# BT_magnetic_switch.net
KiCad netlist of a schematic drawn in EAGLE
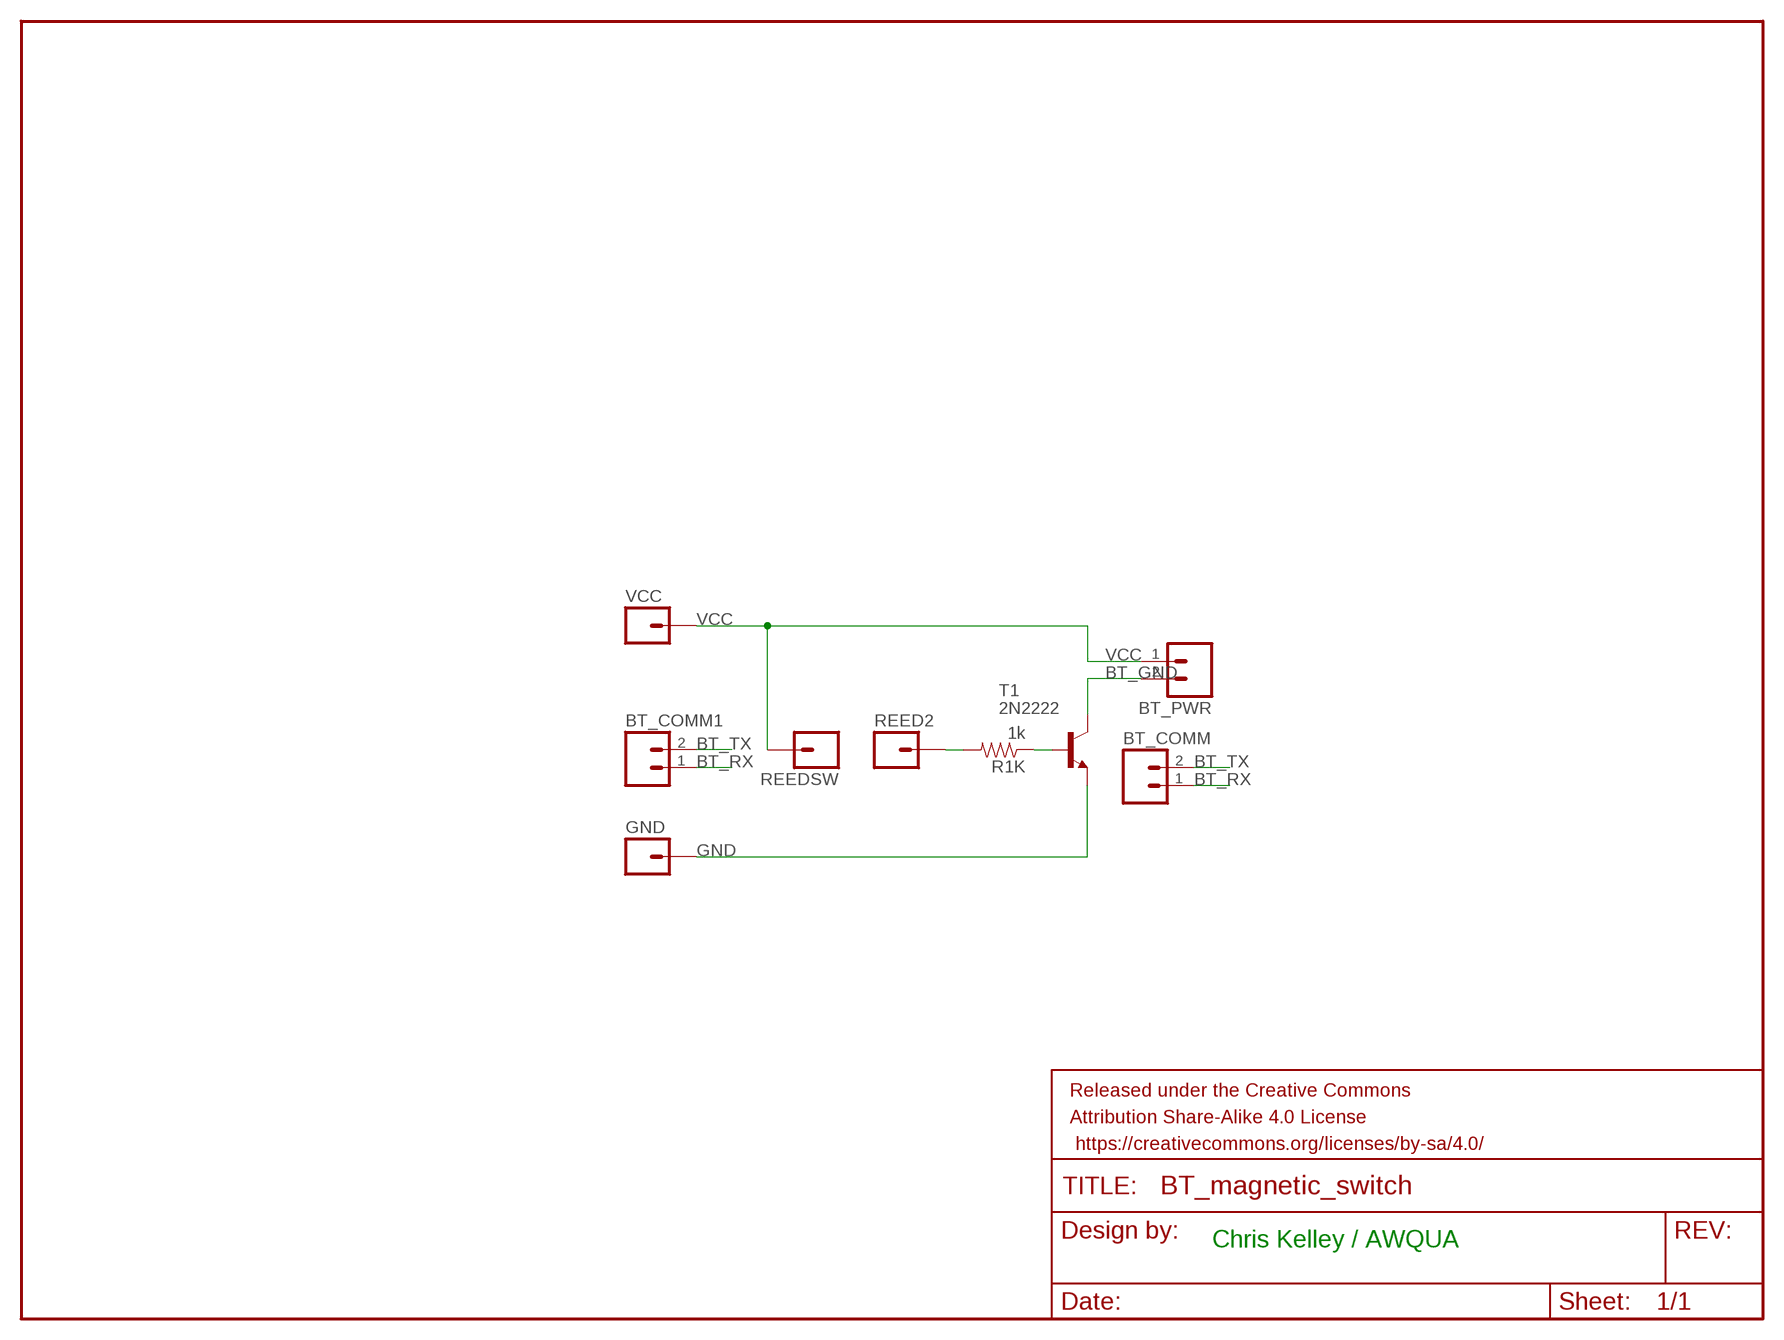
[diagram p0: schematic, sheet 1]

(export (version "E")
  (design (tool "Eeschema 10.0.6"))
  (components
    (comp (ref "BT_COMM")
      (value "M02PTH")
      (footprint "eagle-import:1X02")
      (libsource (lib "eagle-import") (part "M02PTH"))
    )
    (comp (ref "BT_COMM1")
      (value "M02PTH")
      (footprint "eagle-import:1X02")
      (libsource (lib "eagle-import") (part "M02PTH"))
    )
    (comp (ref "BT_PWR")
      (value "M02PTH")
      (footprint "eagle-import:1X02")
      (libsource (lib "eagle-import") (part "M02PTH"))
    )
    (comp (ref "FRAME1")
      (value "FRAME-LETTER")
      (footprint "eagle-import:CREATIVE_COMMONS")
      (libsource (lib "eagle-import") (part "FRAME-LETTER"))
    )
    (comp (ref "GND")
      (value "M01PTH")
      (footprint "eagle-import:1X01")
      (libsource (lib "eagle-import") (part "M01PTH"))
    )
    (comp (ref "R1K")
      (value "1k")
      (footprint "eagle-import:0603-RES")
      (libsource (lib "eagle-import") (part "RESISTOR0603-RES"))
    )
    (comp (ref "REED2")
      (value "M01PTH")
      (footprint "eagle-import:1X01")
      (libsource (lib "eagle-import") (part "M01PTH"))
    )
    (comp (ref "REEDSW")
      (value "M01PTH")
      (footprint "eagle-import:1X01")
      (libsource (lib "eagle-import") (part "M01PTH"))
    )
    (comp (ref "T1")
      (value "2N2222")
      (footprint "eagle-import:TO92-EBC-OVAL")
      (libsource (lib "eagle-import") (part "2N2222"))
    )
    (comp (ref "VCC")
      (value "M01PTH")
      (footprint "eagle-import:1X01")
      (libsource (lib "eagle-import") (part "M01PTH"))
    )
  )
  (nets
    (net (code "1") (name "/BT_GND") (class "Default")
      (node (ref "BT_PWR") (pin "2") (pinfunction "2_2") (pintype "passive"))
      (node (ref "T1") (pin "C") (pinfunction "C_C") (pintype "passive"))
    )
    (net (code "2") (name "/BT_RX") (class "Default")
      (node (ref "BT_COMM") (pin "1") (pinfunction "1_1") (pintype "passive"))
      (node (ref "BT_COMM1") (pin "1") (pinfunction "1_1") (pintype "passive"))
    )
    (net (code "3") (name "/BT_TX") (class "Default")
      (node (ref "BT_COMM") (pin "2") (pinfunction "2_2") (pintype "passive"))
      (node (ref "BT_COMM1") (pin "2") (pinfunction "2_2") (pintype "passive"))
    )
    (net (code "4") (name "/GND") (class "Default")
      (node (ref "GND") (pin "1") (pinfunction "1_1") (pintype "passive"))
      (node (ref "T1") (pin "E") (pinfunction "E_E") (pintype "passive"))
    )
    (net (code "5") (name "/VCC") (class "Default")
      (node (ref "BT_PWR") (pin "1") (pinfunction "1_1") (pintype "passive"))
      (node (ref "REEDSW") (pin "1") (pinfunction "1_1") (pintype "passive"))
      (node (ref "VCC") (pin "1") (pinfunction "1_1") (pintype "passive"))
    )
    (net (code "6") (name "Net-(R1K-Pad1)") (class "Default")
      (node (ref "R1K") (pin "1") (pinfunction "1_1") (pintype "passive"))
      (node (ref "T1") (pin "B") (pinfunction "B_B") (pintype "passive"))
    )
    (net (code "7") (name "Net-(R1K-Pad2)") (class "Default")
      (node (ref "R1K") (pin "2") (pinfunction "2_2") (pintype "passive"))
      (node (ref "REED2") (pin "1") (pinfunction "1_1") (pintype "passive"))
    )
  )
)
